# SRAM_256Kx16_TSOP44.net
KiCad netlist of a schematic drawn in Altium Designer
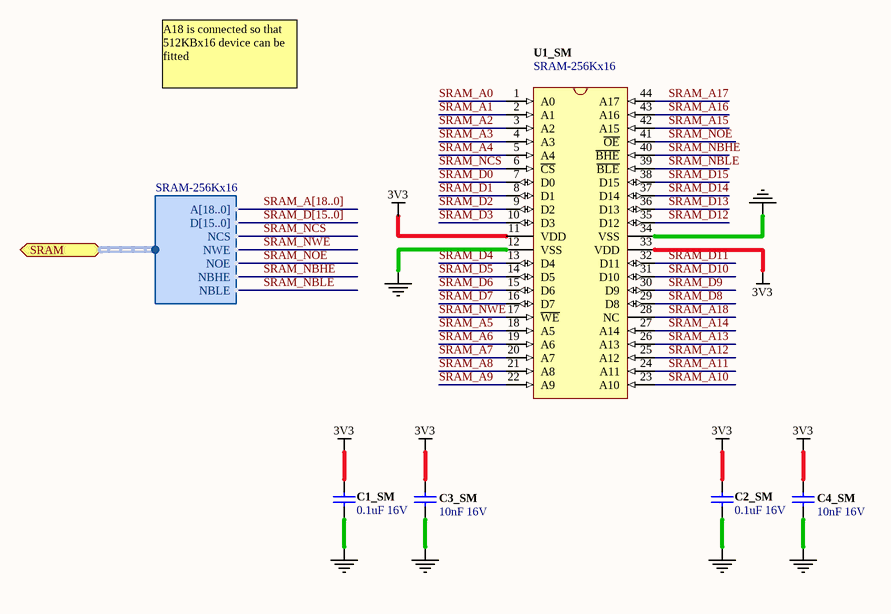
[diagram p0: SRAM_256Kx16_TSOP44.SchDoc]

(export (version "E")
  (design (tool "Eeschema 10.0.6"))
  (components
    (comp (ref "C1_SM")
      (value "0.1uF 16V")
      (footprint "CAPC1005-STAR")
      (description "Capacitor, Ceramic, 0.1uF 10% 16V 0402 (1005) X7R")
      (fields (field (name "TOLERANCE") "10 %"))
      (libsource (lib "AltiumDesignLibrary") (part "CAP-NP"))
    )
    (comp (ref "C2_SM")
      (value "0.1uF 16V")
      (footprint "CAPC1005-STAR")
      (description "Capacitor, Ceramic, 0.1uF 10% 16V 0402 (1005) X7R")
      (fields (field (name "TOLERANCE") "10 %"))
      (libsource (lib "AltiumDesignLibrary") (part "CAP-NP"))
    )
    (comp (ref "C3_SM")
      (value "10nF 16V")
      (footprint "CAPC1005-STAR")
      (description "Capacitor, Ceramic, 10nF 10% 16V 0402 (1005) X7R")
      (fields (field (name "TOLERANCE") "10 %"))
      (libsource (lib "AltiumDesignLibrary") (part "CAP-NP"))
    )
    (comp (ref "C4_SM")
      (value "10nF 16V")
      (footprint "CAPC1005-STAR")
      (description "Capacitor, Ceramic, 10nF 10% 16V 0402 (1005) X7R")
      (fields (field (name "TOLERANCE") "10 %"))
      (libsource (lib "AltiumDesignLibrary") (part "CAP-NP"))
    )
    (comp (ref "U1_SM")
      (value "SRAM-256Kx16")
      (footprint "TSOP80P1176-44")
      (description "K6R4016V1D-TC10T, 256K x 16-Bit SRAM, TSOP44")
      (libsource (lib "AltiumDesignLibrary") (part "K6R4016V1D-T"))
    )
  )
  (nets
    (net (code "2") (name "/SRAM_A0") (class "Default")
      (node (ref "U1_SM") (pin "1") (pinfunction "A0_1") (pintype "input"))
    )
    (net (code "3") (name "/SRAM_A1") (class "Default")
      (node (ref "U1_SM") (pin "2") (pinfunction "A1_2") (pintype "input"))
    )
    (net (code "4") (name "/SRAM_A2") (class "Default")
      (node (ref "U1_SM") (pin "3") (pinfunction "A2_3") (pintype "input"))
    )
    (net (code "5") (name "/SRAM_A3") (class "Default")
      (node (ref "U1_SM") (pin "4") (pinfunction "A3_4") (pintype "input"))
    )
    (net (code "6") (name "/SRAM_A4") (class "Default")
      (node (ref "U1_SM") (pin "5") (pinfunction "A4_5") (pintype "input"))
    )
    (net (code "7") (name "/SRAM_A5") (class "Default")
      (node (ref "U1_SM") (pin "18") (pinfunction "A5_18") (pintype "input"))
    )
    (net (code "8") (name "/SRAM_A6") (class "Default")
      (node (ref "U1_SM") (pin "19") (pinfunction "A6_19") (pintype "input"))
    )
    (net (code "9") (name "/SRAM_A7") (class "Default")
      (node (ref "U1_SM") (pin "20") (pinfunction "A7_20") (pintype "input"))
    )
    (net (code "10") (name "/SRAM_A8") (class "Default")
      (node (ref "U1_SM") (pin "21") (pinfunction "A8_21") (pintype "input"))
    )
    (net (code "11") (name "/SRAM_A9") (class "Default")
      (node (ref "U1_SM") (pin "22") (pinfunction "A9_22") (pintype "input"))
    )
    (net (code "12") (name "/SRAM_A10") (class "Default")
      (node (ref "U1_SM") (pin "23") (pinfunction "A10_23") (pintype "input"))
    )
    (net (code "13") (name "/SRAM_A11") (class "Default")
      (node (ref "U1_SM") (pin "24") (pinfunction "A11_24") (pintype "input"))
    )
    (net (code "14") (name "/SRAM_A12") (class "Default")
      (node (ref "U1_SM") (pin "25") (pinfunction "A12_25") (pintype "input"))
    )
    (net (code "15") (name "/SRAM_A13") (class "Default")
      (node (ref "U1_SM") (pin "26") (pinfunction "A13_26") (pintype "input"))
    )
    (net (code "16") (name "/SRAM_A14") (class "Default")
      (node (ref "U1_SM") (pin "27") (pinfunction "A14_27") (pintype "input"))
    )
    (net (code "17") (name "/SRAM_A15") (class "Default")
      (node (ref "U1_SM") (pin "42") (pinfunction "A15_42") (pintype "input"))
    )
    (net (code "18") (name "/SRAM_A16") (class "Default")
      (node (ref "U1_SM") (pin "43") (pinfunction "A16_43") (pintype "input"))
    )
    (net (code "19") (name "/SRAM_A17") (class "Default")
      (node (ref "U1_SM") (pin "44") (pinfunction "A17_44") (pintype "input"))
    )
    (net (code "20") (name "/SRAM_A18") (class "Default")
      (node (ref "U1_SM") (pin "28") (pinfunction "NC_28") (pintype "passive"))
    )
    (net (code "22") (name "/SRAM_D0") (class "Default")
      (node (ref "U1_SM") (pin "7") (pinfunction "D0_7") (pintype "bidirectional"))
    )
    (net (code "23") (name "/SRAM_D1") (class "Default")
      (node (ref "U1_SM") (pin "8") (pinfunction "D1_8") (pintype "bidirectional"))
    )
    (net (code "24") (name "/SRAM_D2") (class "Default")
      (node (ref "U1_SM") (pin "9") (pinfunction "D2_9") (pintype "bidirectional"))
    )
    (net (code "25") (name "/SRAM_D3") (class "Default")
      (node (ref "U1_SM") (pin "10") (pinfunction "D3_10") (pintype "bidirectional"))
    )
    (net (code "26") (name "/SRAM_D4") (class "Default")
      (node (ref "U1_SM") (pin "13") (pinfunction "D4_13") (pintype "bidirectional"))
    )
    (net (code "27") (name "/SRAM_D5") (class "Default")
      (node (ref "U1_SM") (pin "14") (pinfunction "D5_14") (pintype "bidirectional"))
    )
    (net (code "28") (name "/SRAM_D6") (class "Default")
      (node (ref "U1_SM") (pin "15") (pinfunction "D6_15") (pintype "bidirectional"))
    )
    (net (code "29") (name "/SRAM_D7") (class "Default")
      (node (ref "U1_SM") (pin "16") (pinfunction "D7_16") (pintype "bidirectional"))
    )
    (net (code "30") (name "/SRAM_D8") (class "Default")
      (node (ref "U1_SM") (pin "29") (pinfunction "D8_29") (pintype "bidirectional"))
    )
    (net (code "31") (name "/SRAM_D9") (class "Default")
      (node (ref "U1_SM") (pin "30") (pinfunction "D9_30") (pintype "bidirectional"))
    )
    (net (code "32") (name "/SRAM_D10") (class "Default")
      (node (ref "U1_SM") (pin "31") (pinfunction "D10_31") (pintype "bidirectional"))
    )
    (net (code "33") (name "/SRAM_D11") (class "Default")
      (node (ref "U1_SM") (pin "32") (pinfunction "D11_32") (pintype "bidirectional"))
    )
    (net (code "34") (name "/SRAM_D12") (class "Default")
      (node (ref "U1_SM") (pin "35") (pinfunction "D12_35") (pintype "bidirectional"))
    )
    (net (code "35") (name "/SRAM_D13") (class "Default")
      (node (ref "U1_SM") (pin "36") (pinfunction "D13_36") (pintype "bidirectional"))
    )
    (net (code "36") (name "/SRAM_D14") (class "Default")
      (node (ref "U1_SM") (pin "37") (pinfunction "D14_37") (pintype "bidirectional"))
    )
    (net (code "37") (name "/SRAM_D15") (class "Default")
      (node (ref "U1_SM") (pin "38") (pinfunction "D15_38") (pintype "bidirectional"))
    )
    (net (code "38") (name "/SRAM_NBHE") (class "Default")
      (node (ref "U1_SM") (pin "40") (pinfunction "~{BHE}_40") (pintype "input"))
    )
    (net (code "39") (name "/SRAM_NBLE") (class "Default")
      (node (ref "U1_SM") (pin "39") (pinfunction "~{BLE}_39") (pintype "input"))
    )
    (net (code "40") (name "/SRAM_NCS") (class "Default")
      (node (ref "U1_SM") (pin "6") (pinfunction "~{CS}_6") (pintype "input"))
    )
    (net (code "41") (name "/SRAM_NOE") (class "Default")
      (node (ref "U1_SM") (pin "41") (pinfunction "~{OE}_41") (pintype "input"))
    )
    (net (code "42") (name "/SRAM_NWE") (class "Default")
      (node (ref "U1_SM") (pin "17") (pinfunction "~{WE}_17") (pintype "input"))
    )
    (net (code "45") (name "3V3") (class "Default")
      (node (ref "C1_SM") (pin "1") (pinfunction "1_1") (pintype "passive"))
      (node (ref "C2_SM") (pin "1") (pinfunction "1_1") (pintype "passive"))
      (node (ref "C3_SM") (pin "1") (pinfunction "1_1") (pintype "passive"))
      (node (ref "C4_SM") (pin "1") (pinfunction "1_1") (pintype "passive"))
      (node (ref "U1_SM") (pin "11") (pinfunction "VDD_11") (pintype "power_in"))
      (node (ref "U1_SM") (pin "33") (pinfunction "VDD_33") (pintype "power_in"))
    )
    (net (code "46") (name "GND") (class "Default")
      (node (ref "C1_SM") (pin "2") (pinfunction "2_2") (pintype "passive"))
      (node (ref "C2_SM") (pin "2") (pinfunction "2_2") (pintype "passive"))
      (node (ref "C3_SM") (pin "2") (pinfunction "2_2") (pintype "passive"))
      (node (ref "C4_SM") (pin "2") (pinfunction "2_2") (pintype "passive"))
      (node (ref "U1_SM") (pin "12") (pinfunction "VSS_12") (pintype "power_in"))
      (node (ref "U1_SM") (pin "34") (pinfunction "VSS_34") (pintype "power_in"))
    )
  )
)
